# CH32V003F4U6_I2C_PrototypeBoard.net
KiCad netlist of a schematic drawn in EasyEDA Pro
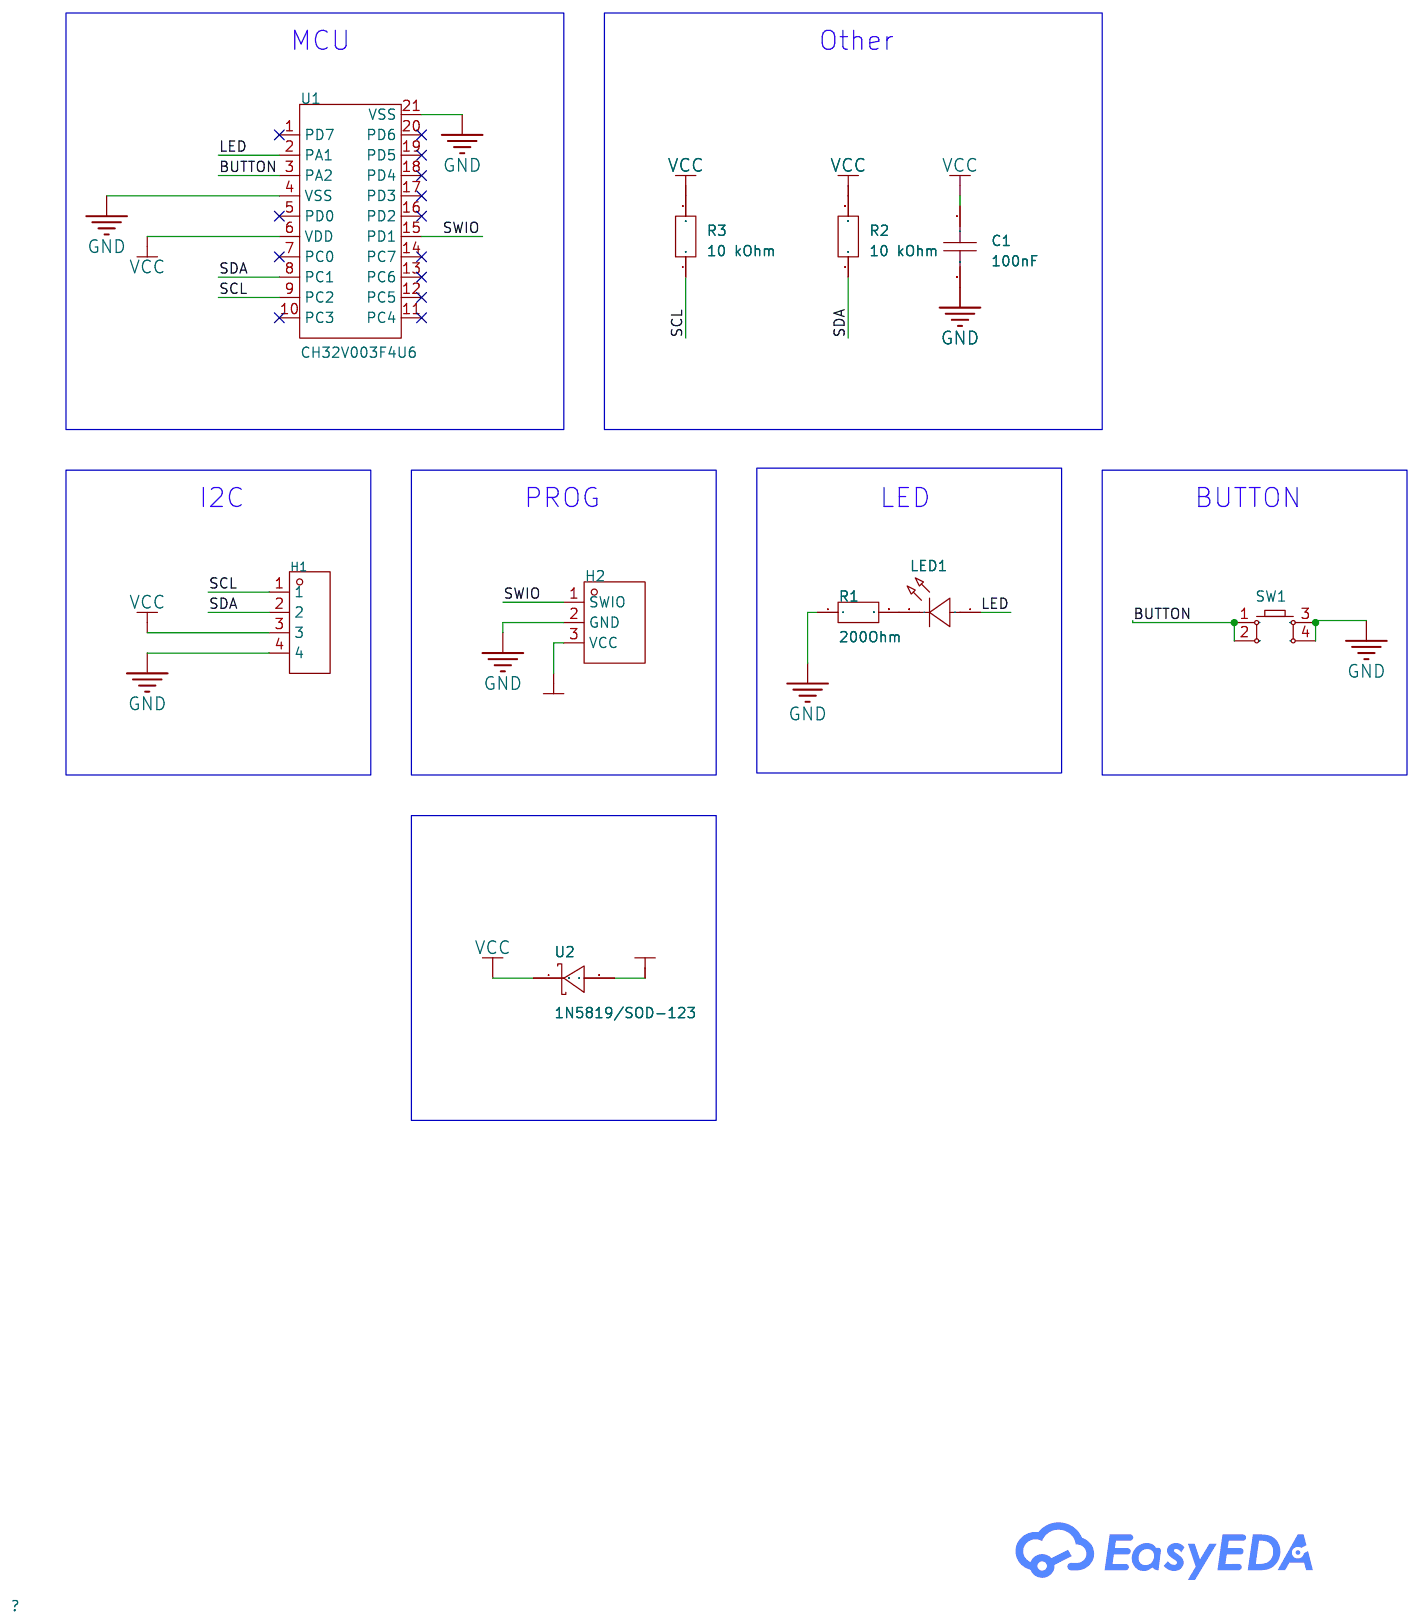
[diagram p0: schematic sheet]

(export (version "E")
  (design (tool "Eeschema 10.0.6"))
  (components
    (comp (ref "C1")
      (value "100nF")
      (footprint "easyedapro:C0805")
      (libsource (lib "easyedapro") (part "CAP"))
    )
    (comp (ref "H1")
      (value "~")
      (footprint "easyedapro:HDR-TH_4P-P2.54-V-F")
      (libsource (lib "easyedapro") (part "2.54-1*4P母"))
    )
    (comp (ref "H2")
      (value "~")
      (footprint "easyedapro:HDR-TH_3P-P2.54-V-M")
      (libsource (lib "easyedapro") (part "CH32V003 SWIO Header"))
    )
    (comp (ref "LED1")
      (value "4dcf0610a8494475a8d28c2e9e951178")
      (footprint "easyedapro:LED-SMD_L3.2-W2.4-R-RD")
      (fields
        (field (name "Manufacturer Part") "42-21SYGC/S530-E2/TR8(GH)")
        (field (name "Manufacturer") "EVERLIGHT(亿光)")
      )
      (libsource (lib "easyedapro") (part "LED 3528 1210"))
    )
    (comp (ref "R1")
      (value "200Ohm")
      (footprint "easyedapro:R0805")
      (libsource (lib "easyedapro") (part "Resistor 0805"))
    )
    (comp (ref "R2")
      (value "10 kOhm")
      (footprint "easyedapro:R0805")
      (libsource (lib "easyedapro") (part "Resistor 0805"))
    )
    (comp (ref "R3")
      (value "10 kOhm")
      (footprint "easyedapro:R0805")
      (libsource (lib "easyedapro") (part "Resistor 0805"))
    )
    (comp (ref "SW1")
      (value "~")
      (footprint "easyedapro:SW-SMD_4P-L6.0-W6.0-P4.50-LS9.0-2")
      (libsource (lib "easyedapro") (part "轻触按键"))
    )
    (comp (ref "U1")
      (value "CH32V003F4U6")
      (footprint "easyedapro:QFN-20_L3.0-W3.0-P0.40-TL-EP1.7")
      (description "CPU Core:RISC-V CPU Maximum Speed:48MHz Program Storage Size:16KB Number of I/O:18 Applications:-")
      (fields (field (name "Manufacturer") "WCH(南京沁恒)"))
      (libsource (lib "easyedapro") (part "CH32V003F4U6"))
    )
    (comp (ref "U2")
      (value "1N5819/SOD-123")
      (footprint "easyedapro:SOD-123_L2.7-W1.7-LS3.8-RD")
      (libsource (lib "easyedapro") (part "1N5819/SOD-123"))
    )
  )
  (nets
    (net (code "1") (name "/BUTTON") (class "Default")
      (node (ref "SW1") (pin "1") (pinfunction "1_1") (pintype "input"))
      (node (ref "SW1") (pin "2") (pinfunction "2_2") (pintype "input"))
      (node (ref "U1") (pin "3") (pinfunction "PA2_3") (pintype "unspecified"))
    )
    (net (code "2") (name "/LED") (class "Default")
      (node (ref "LED1") (pin "1") (pinfunction "+_1") (pintype "unspecified"))
      (node (ref "U1") (pin "2") (pinfunction "PA1_2") (pintype "unspecified"))
    )
    (net (code "3") (name "/SCL") (class "Default")
      (node (ref "H1") (pin "1") (pinfunction "1_1") (pintype "input"))
      (node (ref "R3") (pin "1") (pinfunction "1_1") (pintype "unspecified"))
      (node (ref "U1") (pin "9") (pinfunction "PC2_9") (pintype "unspecified"))
    )
    (net (code "4") (name "/SDA") (class "Default")
      (node (ref "H1") (pin "2") (pinfunction "2_2") (pintype "input"))
      (node (ref "R2") (pin "1") (pinfunction "1_1") (pintype "unspecified"))
      (node (ref "U1") (pin "8") (pinfunction "PC1_8") (pintype "unspecified"))
    )
    (net (code "5") (name "/SWIO") (class "Default")
      (node (ref "H2") (pin "1") (pinfunction "SWIO_1") (pintype "unspecified"))
      (node (ref "U1") (pin "15") (pinfunction "PD1_15") (pintype "unspecified"))
    )
    (net (code "6") (name "GND") (class "Default")
      (node (ref "C1") (pin "2") (pinfunction "2_2") (pintype "input"))
      (node (ref "H1") (pin "4") (pinfunction "4_4") (pintype "input"))
      (node (ref "H2") (pin "2") (pinfunction "GND_2") (pintype "unspecified"))
      (node (ref "R1") (pin "1") (pinfunction "1_1") (pintype "unspecified"))
      (node (ref "SW1") (pin "3") (pinfunction "3_3") (pintype "input"))
      (node (ref "SW1") (pin "4") (pinfunction "4_4") (pintype "input"))
      (node (ref "U1") (pin "21") (pinfunction "VSS_21") (pintype "unspecified"))
      (node (ref "U1") (pin "4") (pinfunction "VSS_4") (pintype "unspecified"))
    )
    (net (code "7") (name "Net-(LED1--)") (class "Default")
      (node (ref "LED1") (pin "2") (pinfunction "-_2") (pintype "unspecified"))
      (node (ref "R1") (pin "2") (pinfunction "2_2") (pintype "unspecified"))
    )
    (net (code "8") (name "VCC") (class "Default")
      (node (ref "C1") (pin "1") (pinfunction "1_1") (pintype "input"))
      (node (ref "H1") (pin "3") (pinfunction "3_3") (pintype "input"))
      (node (ref "R2") (pin "2") (pinfunction "2_2") (pintype "unspecified"))
      (node (ref "R3") (pin "2") (pinfunction "2_2") (pintype "unspecified"))
      (node (ref "U1") (pin "6") (pinfunction "VDD_6") (pintype "unspecified"))
      (node (ref "U2") (pin "1") (pinfunction "C_1") (pintype "unspecified"))
    )
    (net (code "9") (name "VIN") (class "Default")
      (node (ref "H2") (pin "3") (pinfunction "VCC_3") (pintype "unspecified"))
      (node (ref "U2") (pin "2") (pinfunction "A_2") (pintype "unspecified"))
    )
    (net (code "10") (name "unconnected-(U1-PC0-Pad7)") (class "Default")
      (node (ref "U1") (pin "7") (pinfunction "PC0_7") (pintype "unspecified+no_connect"))
    )
    (net (code "11") (name "unconnected-(U1-PC3-Pad10)") (class "Default")
      (node (ref "U1") (pin "10") (pinfunction "PC3_10") (pintype "unspecified+no_connect"))
    )
    (net (code "12") (name "unconnected-(U1-PC4-Pad11)") (class "Default")
      (node (ref "U1") (pin "11") (pinfunction "PC4_11") (pintype "unspecified+no_connect"))
    )
    (net (code "13") (name "unconnected-(U1-PC5-Pad12)") (class "Default")
      (node (ref "U1") (pin "12") (pinfunction "PC5_12") (pintype "unspecified+no_connect"))
    )
    (net (code "14") (name "unconnected-(U1-PC6-Pad13)") (class "Default")
      (node (ref "U1") (pin "13") (pinfunction "PC6_13") (pintype "unspecified+no_connect"))
    )
    (net (code "15") (name "unconnected-(U1-PC7-Pad14)") (class "Default")
      (node (ref "U1") (pin "14") (pinfunction "PC7_14") (pintype "unspecified+no_connect"))
    )
    (net (code "16") (name "unconnected-(U1-PD0-Pad5)") (class "Default")
      (node (ref "U1") (pin "5") (pinfunction "PD0_5") (pintype "unspecified+no_connect"))
    )
    (net (code "17") (name "unconnected-(U1-PD2-Pad16)") (class "Default")
      (node (ref "U1") (pin "16") (pinfunction "PD2_16") (pintype "unspecified+no_connect"))
    )
    (net (code "18") (name "unconnected-(U1-PD3-Pad17)") (class "Default")
      (node (ref "U1") (pin "17") (pinfunction "PD3_17") (pintype "unspecified+no_connect"))
    )
    (net (code "19") (name "unconnected-(U1-PD4-Pad18)") (class "Default")
      (node (ref "U1") (pin "18") (pinfunction "PD4_18") (pintype "unspecified+no_connect"))
    )
    (net (code "20") (name "unconnected-(U1-PD5-Pad19)") (class "Default")
      (node (ref "U1") (pin "19") (pinfunction "PD5_19") (pintype "unspecified+no_connect"))
    )
    (net (code "21") (name "unconnected-(U1-PD6-Pad20)") (class "Default")
      (node (ref "U1") (pin "20") (pinfunction "PD6_20") (pintype "unspecified+no_connect"))
    )
    (net (code "22") (name "unconnected-(U1-PD7-Pad1)") (class "Default")
      (node (ref "U1") (pin "1") (pinfunction "PD7_1") (pintype "unspecified+no_connect"))
    )
  )
)
